# 12V_DC.net
KiCad netlist of a schematic drawn in Altium Designer
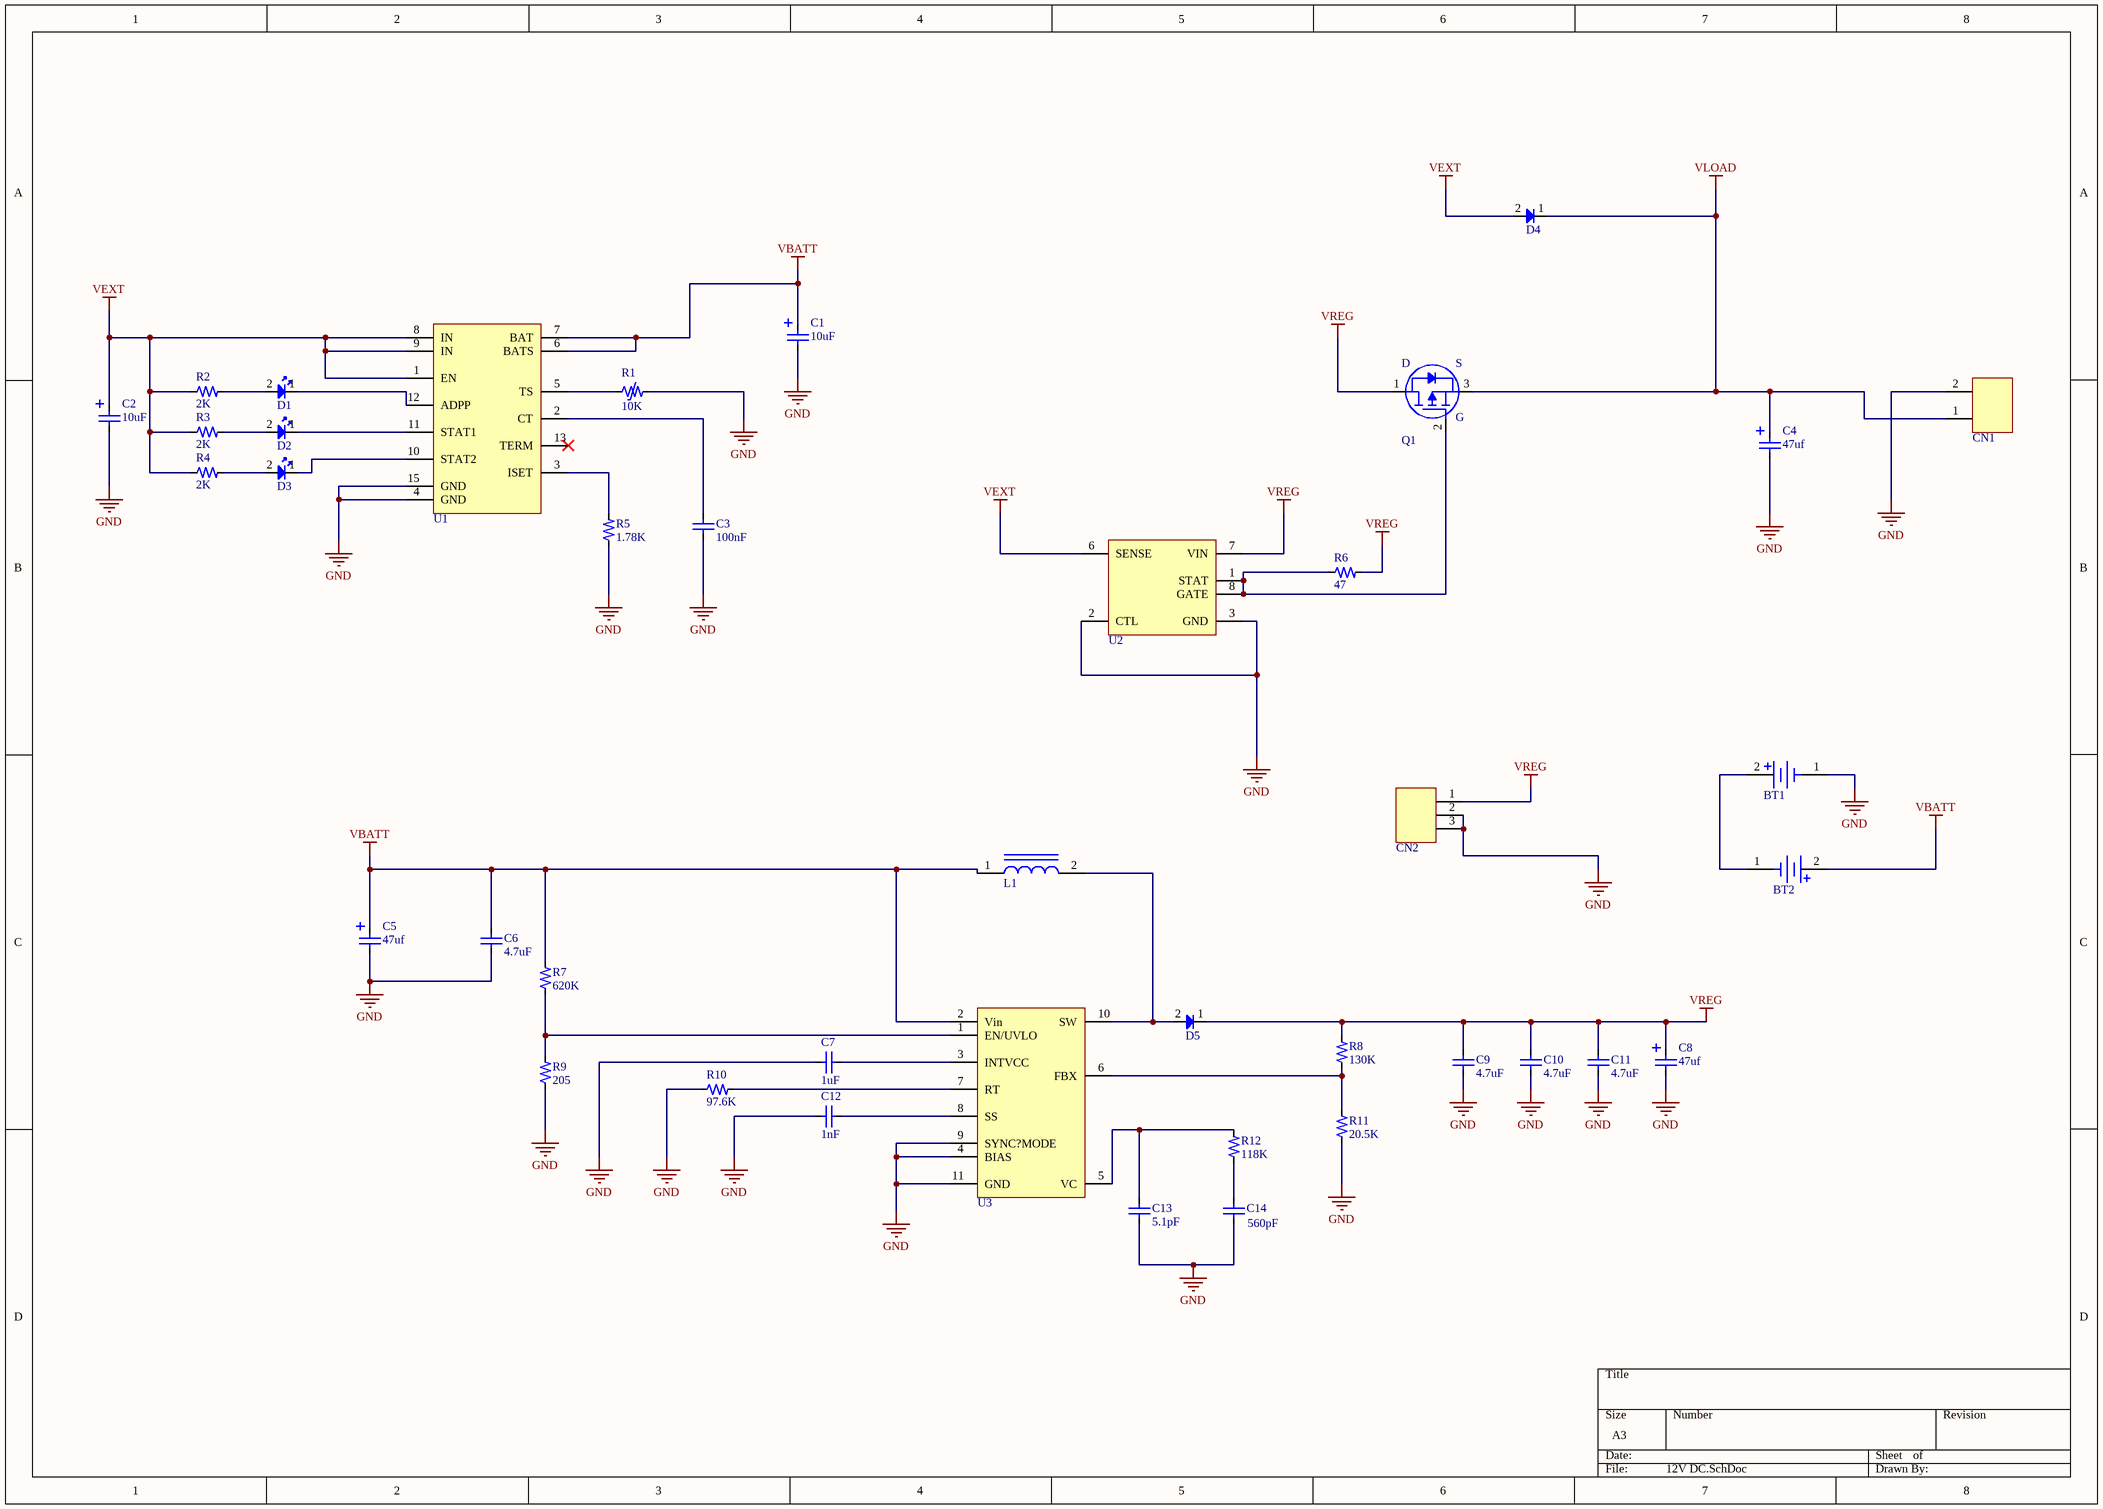
[diagram p0: 12V DC.SchDoc]

(export (version "E")
  (design (tool "Eeschema 10.0.6"))
  (components
    (comp (ref "BT1")
      (value "BK-18650-PC2")
      (footprint "18650")
      (libsource (lib "Database_Libs1") (part "BK-18650-PC2"))
    )
    (comp (ref "BT2")
      (value "BK-18650-PC2")
      (footprint "18650")
      (libsource (lib "Database_Libs1") (part "BK-18650-PC2"))
    )
    (comp (ref "C1")
      (value "10uF")
      (footprint "CAP_3216")
      (fields
        (field (name "VOLTAGE") "10V")
        (field (name "TOLERANCE") "±10%")
        (field (name "Comment") "CAP_POL")
      )
      (libsource (lib "Database_Libs1") (part "CAP_POL"))
    )
    (comp (ref "C2")
      (value "10uF")
      (footprint "CAP_3216")
      (fields
        (field (name "VOLTAGE") "10V")
        (field (name "TOLERANCE") "±10%")
        (field (name "Comment") "CAP_POL")
      )
      (libsource (lib "Database_Libs1") (part "CAP_POL"))
    )
    (comp (ref "C3")
      (value "100nF")
      (footprint "Capacitor_0402")
      (fields
        (field (name "VOLTAGE") "50V")
        (field (name "TOLERANCE") "±10%")
        (field (name "Comment") "Capacitor_0402")
      )
      (libsource (lib "Database_Libs1") (part "Capacitor_0402"))
    )
    (comp (ref "C4")
      (value "47uf")
      (footprint "CAP_1206")
      (fields
        (field (name "VOLTAGE") "6.3V")
        (field (name "TOLERANCE") "±20%")
        (field (name "Comment") "CAP_1206")
      )
      (libsource (lib "Database_Libs1") (part "CAP_1206"))
    )
    (comp (ref "C5")
      (value "47uf")
      (footprint "CAP_1206")
      (fields
        (field (name "VOLTAGE") "6.3V")
        (field (name "TOLERANCE") "±20%")
        (field (name "Comment") "CAP_1206")
      )
      (libsource (lib "Database_Libs1") (part "CAP_1206"))
    )
    (comp (ref "C6")
      (value "4.7uF")
      (footprint "Capacitor_0603")
      (fields
        (field (name "VOLTAGE") "10V")
        (field (name "TOLERANCE") "±10%")
        (field (name "Comment") "Capacitor_0603")
      )
      (libsource (lib "Database_Libs1") (part "Capacitor_0603"))
    )
    (comp (ref "C7")
      (value "1uF")
      (footprint "Capacitor_0402")
      (fields
        (field (name "VOLTAGE") "6.3V")
        (field (name "TOLERANCE") "±10%")
        (field (name "Comment") "Capacitor_0402")
      )
      (libsource (lib "Database_Libs1") (part "Capacitor_0402"))
    )
    (comp (ref "C8")
      (value "47uf")
      (footprint "CAP_1206")
      (fields
        (field (name "VOLTAGE") "6.3V")
        (field (name "TOLERANCE") "±20%")
        (field (name "Comment") "CAP_1206")
      )
      (libsource (lib "Database_Libs1") (part "CAP_1206"))
    )
    (comp (ref "C9")
      (value "4.7uF")
      (footprint "Capacitor_0603")
      (fields
        (field (name "VOLTAGE") "10V")
        (field (name "TOLERANCE") "±10%")
        (field (name "Comment") "Capacitor_0603")
      )
      (libsource (lib "Database_Libs1") (part "Capacitor_0603"))
    )
    (comp (ref "C10")
      (value "4.7uF")
      (footprint "Capacitor_0603")
      (fields
        (field (name "VOLTAGE") "10V")
        (field (name "TOLERANCE") "±10%")
        (field (name "Comment") "Capacitor_0603")
      )
      (libsource (lib "Database_Libs1") (part "Capacitor_0603"))
    )
    (comp (ref "C11")
      (value "4.7uF")
      (footprint "Capacitor_0603")
      (fields
        (field (name "VOLTAGE") "10V")
        (field (name "TOLERANCE") "±10%")
        (field (name "Comment") "Capacitor_0603")
      )
      (libsource (lib "Database_Libs1") (part "Capacitor_0603"))
    )
    (comp (ref "C12")
      (value "1nF")
      (footprint "Capacitor_0402")
      (fields
        (field (name "VOLTAGE") "50v")
        (field (name "TOLERANCE") "±10%")
        (field (name "Comment") "Capacitor_0402")
      )
      (libsource (lib "Database_Libs1") (part "Capacitor_0402"))
    )
    (comp (ref "C13")
      (value "5.1pF")
      (footprint "Capacitor_0402")
      (fields
        (field (name "VOLTAGE") "50V")
        (field (name "TOLERANCE") "±0.25pF")
        (field (name "Comment") "Capacitor_0402")
      )
      (libsource (lib "Database_Libs1") (part "Capacitor_0402"))
    )
    (comp (ref "C14")
      (value "560pF")
      (footprint "Capacitor_0402")
      (fields (field (name "VOLTAGE") "50V") (field (name "Comment") "Capacitor_0402"))
      (libsource (lib "Database_Libs1") (part "Capacitor_0402"))
    )
    (comp (ref "CN1")
      (value "2 Position Wire Terminal")
      (footprint "282834-2")
      (libsource (lib "Database_Libs1") (part "2 Position Wire Terminal"))
    )
    (comp (ref "CN2")
      (value "PJ-202A")
      (footprint "PJ-202A")
      (libsource (lib "Database_Libs1") (part "PJ-202A"))
    )
    (comp (ref "D1")
      (value "LED")
      (footprint "LED_0402")
      (fields (field (name "VOLTAGE") "2V") (field (name "POWER") "0.06W"))
      (libsource (lib "Database_Libs1") (part "LED"))
    )
    (comp (ref "D2")
      (value "LED")
      (footprint "LED_0402")
      (fields (field (name "VOLTAGE") "2V") (field (name "POWER") "0.06W"))
      (libsource (lib "Database_Libs1") (part "LED"))
    )
    (comp (ref "D3")
      (value "LED")
      (footprint "LED_0402")
      (fields (field (name "VOLTAGE") "2V") (field (name "POWER") "0.06W"))
      (libsource (lib "Database_Libs1") (part "LED"))
    )
    (comp (ref "D4")
      (value "CDBA240LL-HF")
      (footprint "DO-214AC")
      (fields (field (name "VOLTAGE") "40v"))
      (libsource (lib "Database_Libs1") (part "CDBA240LL-HF"))
    )
    (comp (ref "D5")
      (value "CDBA240LL-HF")
      (footprint "DO-214AC")
      (fields (field (name "VOLTAGE") "40v"))
      (libsource (lib "Database_Libs1") (part "CDBA240LL-HF"))
    )
    (comp (ref "L1")
      (value "IHLP4040DZER5R6M01")
      (footprint "Inductor_4040")
      (fields (field (name "TOLERANCE") "±20%"))
      (libsource (lib "Database_Libs1") (part "IHLP4040DZER5R6M01"))
    )
    (comp (ref "Q1")
      (value "DMP2045U-7")
      (footprint "SOT-23")
      (description "P-Channel 20 V 4.3A (Ta) 800mW (Ta) Surface Mount SOT-23-3")
      (fields (field (name "VOLTAGE") "20 V"))
      (libsource (lib "Database_Libs1") (part "DMP2045U-7"))
    )
    (comp (ref "R1")
      (value "10K")
      (footprint "Resistor_0402")
      (fields
        (field (name "POWER") "66 mW")
        (field (name "TOLERANCE") "±3%")
        (field (name "Comment") "Thermistor_0402")
      )
      (libsource (lib "Database_Libs1") (part "Thermistor_0402"))
    )
    (comp (ref "R2")
      (value "2K")
      (footprint "Resistor_0603")
      (fields
        (field (name "POWER") "100mW")
        (field (name "TOLERANCE") "±1%")
        (field (name "Comment") "Resistor_0603")
      )
      (libsource (lib "Database_Libs1") (part "Resistor_0603"))
    )
    (comp (ref "R3")
      (value "2K")
      (footprint "Resistor_0603")
      (fields
        (field (name "POWER") "100mW")
        (field (name "TOLERANCE") "±1%")
        (field (name "Comment") "Resistor_0603")
      )
      (libsource (lib "Database_Libs1") (part "Resistor_0603"))
    )
    (comp (ref "R4")
      (value "2K")
      (footprint "Resistor_0603")
      (fields
        (field (name "POWER") "100mW")
        (field (name "TOLERANCE") "±1%")
        (field (name "Comment") "Resistor_0603")
      )
      (libsource (lib "Database_Libs1") (part "Resistor_0603"))
    )
    (comp (ref "R5")
      (value "1.78K")
      (footprint "Resistor_0603")
      (fields
        (field (name "POWER") "100mW")
        (field (name "TOLERANCE") "±1%")
        (field (name "Comment") "Resistor_0603")
      )
      (libsource (lib "Database_Libs1") (part "Resistor_0603"))
    )
    (comp (ref "R6")
      (value "47")
      (footprint "Resistor_0603")
      (fields
        (field (name "POWER") "100mW")
        (field (name "TOLERANCE") "±1%")
        (field (name "Comment") "Resistor_0603")
      )
      (libsource (lib "Database_Libs1") (part "Resistor_0603"))
    )
    (comp (ref "R7")
      (value "620K")
      (footprint "Resistor_0603")
      (fields
        (field (name "POWER") "100mW")
        (field (name "TOLERANCE") "±1%")
        (field (name "Comment") "Resistor_0603")
      )
      (libsource (lib "Database_Libs1") (part "Resistor_0603"))
    )
    (comp (ref "R8")
      (value "130K")
      (footprint "Resistor_0402")
      (fields
        (field (name "POWER") "100mW")
        (field (name "TOLERANCE") "±1%")
        (field (name "Comment") "Resistor_0402")
      )
      (libsource (lib "Database_Libs1") (part "Resistor_0402"))
    )
    (comp (ref "R9")
      (value "205")
      (footprint "Resistor_0603")
      (fields
        (field (name "POWER") "100mW")
        (field (name "TOLERANCE") "±1%")
        (field (name "Comment") "Resistor_0603")
      )
      (libsource (lib "Database_Libs1") (part "Resistor_0603"))
    )
    (comp (ref "R10")
      (value "97.6K")
      (footprint "Resistor_0402")
      (fields
        (field (name "POWER") "63mW")
        (field (name "TOLERANCE") "±1%")
        (field (name "Comment") "Resistor_0402")
      )
      (libsource (lib "Database_Libs1") (part "Resistor_0402"))
    )
    (comp (ref "R11")
      (value "20.5K")
      (footprint "Resistor_0603")
      (fields
        (field (name "POWER") "100mW")
        (field (name "TOLERANCE") "±1%")
        (field (name "Comment") "Resistor_0603")
      )
      (libsource (lib "Database_Libs1") (part "Resistor_0603"))
    )
    (comp (ref "R12")
      (value "118K")
      (footprint "Resistor_0402")
      (fields
        (field (name "POWER") "100mW")
        (field (name "TOLERANCE") "±1%")
        (field (name "Comment") "Resistor_0402")
      )
      (libsource (lib "Database_Libs1") (part "Resistor_0402"))
    )
    (comp (ref "U1")
      (value "AAT3663IWO-8.4-2-T1")
      (footprint "14-TDFN")
      (libsource (lib "Database_Libs1") (part "AAT3663IWO-8.4-2-T1"))
    )
    (comp (ref "U2")
      (value "LTC4414EMS8#PBF")
      (footprint "8-MSOP")
      (libsource (lib "Database_Libs1") (part "LTC4414EMS8#PBF"))
    )
    (comp (ref "U3")
      (value "LT8362EDD#PBF")
      (footprint "10-DFN")
      (libsource (lib "Database_Libs1") (part "LT8362EDD#PBF"))
    )
  )
  (nets
    (net (code "1") (name "GND") (class "Default")
      (node (ref "BT1") (pin "1") (pinfunction "NEG_1") (pintype "passive"))
      (node (ref "C1") (pin "1") (pinfunction "1_1") (pintype "passive"))
      (node (ref "C10") (pin "2") (pinfunction "2_2") (pintype "passive"))
      (node (ref "C11") (pin "1") (pinfunction "1_1") (pintype "passive"))
      (node (ref "C12") (pin "1") (pinfunction "1_1") (pintype "passive"))
      (node (ref "C13") (pin "1") (pinfunction "1_1") (pintype "passive"))
      (node (ref "C14") (pin "1") (pinfunction "1_1") (pintype "passive"))
      (node (ref "C2") (pin "1") (pinfunction "1_1") (pintype "passive"))
      (node (ref "C3") (pin "1") (pinfunction "1_1") (pintype "passive"))
      (node (ref "C4") (pin "1") (pinfunction "1_1") (pintype "passive"))
      (node (ref "C5") (pin "1") (pinfunction "1_1") (pintype "passive"))
      (node (ref "C6") (pin "1") (pinfunction "1_1") (pintype "passive"))
      (node (ref "C7") (pin "1") (pinfunction "1_1") (pintype "passive"))
      (node (ref "C8") (pin "1") (pinfunction "1_1") (pintype "passive"))
      (node (ref "C9") (pin "1") (pinfunction "1_1") (pintype "passive"))
      (node (ref "CN1") (pin "2") (pinfunction "2_2") (pintype "passive"))
      (node (ref "CN2") (pin "2") (pintype "passive"))
      (node (ref "CN2") (pin "3") (pintype "passive"))
      (node (ref "R1") (pin "2") (pinfunction "2_2") (pintype "passive"))
      (node (ref "R10") (pin "1") (pinfunction "1_1") (pintype "passive"))
      (node (ref "R11") (pin "1") (pinfunction "1_1") (pintype "passive"))
      (node (ref "R5") (pin "1") (pinfunction "1_1") (pintype "passive"))
      (node (ref "R9") (pin "1") (pinfunction "1_1") (pintype "passive"))
      (node (ref "U1") (pin "15") (pinfunction "GND_15") (pintype "passive"))
      (node (ref "U1") (pin "4") (pinfunction "GND_4") (pintype "passive"))
      (node (ref "U2") (pin "2") (pinfunction "CTL_2") (pintype "power_in"))
      (node (ref "U2") (pin "3") (pinfunction "GND_3") (pintype "power_in"))
      (node (ref "U3") (pin "11") (pinfunction "GND_11") (pintype "passive"))
      (node (ref "U3") (pin "4") (pinfunction "BIAS_4") (pintype "passive"))
      (node (ref "U3") (pin "9") (pinfunction "SYNC?MODE_9") (pintype "passive"))
    )
    (net (code "2") (name "Net-(BT1-POS)") (class "Default")
      (node (ref "BT1") (pin "2") (pinfunction "POS_2") (pintype "passive"))
      (node (ref "BT2") (pin "1") (pinfunction "NEG_1") (pintype "passive"))
    )
    (net (code "3") (name "Net-(C14-Pad2)") (class "Default")
      (node (ref "C14") (pin "2") (pinfunction "2_2") (pintype "passive"))
      (node (ref "R12") (pin "1") (pinfunction "1_1") (pintype "passive"))
    )
    (net (code "4") (name "Net-(D1-Pad2)") (class "Default")
      (node (ref "D1") (pin "2") (pinfunction "2_2") (pintype "passive"))
      (node (ref "R2") (pin "2") (pinfunction "2_2") (pintype "passive"))
    )
    (net (code "5") (name "Net-(D2-Pad2)") (class "Default")
      (node (ref "D2") (pin "2") (pinfunction "2_2") (pintype "passive"))
      (node (ref "R3") (pin "2") (pinfunction "2_2") (pintype "passive"))
    )
    (net (code "6") (name "Net-(D3-Pad2)") (class "Default")
      (node (ref "D3") (pin "2") (pinfunction "2_2") (pintype "passive"))
      (node (ref "R4") (pin "2") (pinfunction "2_2") (pintype "passive"))
    )
    (net (code "7") (name "Net-(Q1-G)") (class "Default")
      (node (ref "Q1") (pin "2") (pinfunction "G_2") (pintype "passive"))
      (node (ref "R6") (pin "1") (pinfunction "1_1") (pintype "passive"))
      (node (ref "U2") (pin "1") (pinfunction "STAT_1") (pintype "power_in"))
      (node (ref "U2") (pin "8") (pinfunction "GATE_8") (pintype "passive"))
    )
    (net (code "8") (name "Net-(U1-ADPP)") (class "Default")
      (node (ref "D1") (pin "1") (pinfunction "1_1") (pintype "passive"))
      (node (ref "U1") (pin "12") (pinfunction "ADPP_12") (pintype "passive"))
    )
    (net (code "9") (name "Net-(U1-CT)") (class "Default")
      (node (ref "C3") (pin "2") (pinfunction "2_2") (pintype "passive"))
      (node (ref "U1") (pin "2") (pinfunction "CT_2") (pintype "passive"))
    )
    (net (code "10") (name "Net-(U1-ISET)") (class "Default")
      (node (ref "R5") (pin "2") (pinfunction "2_2") (pintype "passive"))
      (node (ref "U1") (pin "3") (pinfunction "ISET_3") (pintype "passive"))
    )
    (net (code "11") (name "Net-(U1-STAT1)") (class "Default")
      (node (ref "D2") (pin "1") (pinfunction "1_1") (pintype "passive"))
      (node (ref "U1") (pin "11") (pinfunction "STAT1_11") (pintype "passive"))
    )
    (net (code "12") (name "Net-(U1-STAT2)") (class "Default")
      (node (ref "D3") (pin "1") (pinfunction "1_1") (pintype "passive"))
      (node (ref "U1") (pin "10") (pinfunction "STAT2_10") (pintype "passive"))
    )
    (net (code "13") (name "Net-(U1-TS)") (class "Default")
      (node (ref "R1") (pin "1") (pinfunction "1_1") (pintype "passive"))
      (node (ref "U1") (pin "5") (pinfunction "TS_5") (pintype "passive"))
    )
    (net (code "14") (name "Net-(U3-EN{slash}UVLO)") (class "Default")
      (node (ref "R7") (pin "1") (pinfunction "1_1") (pintype "passive"))
      (node (ref "R9") (pin "2") (pinfunction "2_2") (pintype "passive"))
      (node (ref "U3") (pin "1") (pinfunction "EN/UVLO_1") (pintype "passive"))
    )
    (net (code "15") (name "Net-(U3-FBX)") (class "Default")
      (node (ref "R11") (pin "2") (pinfunction "2_2") (pintype "passive"))
      (node (ref "R8") (pin "1") (pinfunction "1_1") (pintype "passive"))
      (node (ref "U3") (pin "6") (pinfunction "FBX_6") (pintype "passive"))
    )
    (net (code "16") (name "Net-(U3-INTVCC)") (class "Default")
      (node (ref "C7") (pin "2") (pinfunction "2_2") (pintype "passive"))
      (node (ref "U3") (pin "3") (pinfunction "INTVCC_3") (pintype "passive"))
    )
    (net (code "17") (name "Net-(U3-RT)") (class "Default")
      (node (ref "R10") (pin "2") (pinfunction "2_2") (pintype "passive"))
      (node (ref "U3") (pin "7") (pinfunction "RT_7") (pintype "passive"))
    )
    (net (code "18") (name "Net-(U3-SS)") (class "Default")
      (node (ref "C12") (pin "2") (pinfunction "2_2") (pintype "passive"))
      (node (ref "U3") (pin "8") (pinfunction "SS_8") (pintype "passive"))
    )
    (net (code "19") (name "Net-(U3-SW)") (class "Default")
      (node (ref "D5") (pin "2") (pinfunction "2_2") (pintype "passive"))
      (node (ref "L1") (pin "2") (pinfunction "2_2") (pintype "passive"))
      (node (ref "U3") (pin "10") (pinfunction "SW_10") (pintype "passive"))
    )
    (net (code "20") (name "Net-(U3-VC)") (class "Default")
      (node (ref "C13") (pin "2") (pinfunction "2_2") (pintype "passive"))
      (node (ref "R12") (pin "2") (pinfunction "2_2") (pintype "passive"))
      (node (ref "U3") (pin "5") (pinfunction "VC_5") (pintype "passive"))
    )
    (net (code "21") (name "VBATT") (class "Default")
      (node (ref "BT2") (pin "2") (pinfunction "POS_2") (pintype "passive"))
      (node (ref "C1") (pin "2") (pinfunction "2_2") (pintype "passive"))
      (node (ref "C5") (pin "2") (pinfunction "2_2") (pintype "passive"))
      (node (ref "C6") (pin "2") (pinfunction "2_2") (pintype "passive"))
      (node (ref "L1") (pin "1") (pinfunction "1_1") (pintype "passive"))
      (node (ref "R7") (pin "2") (pinfunction "2_2") (pintype "passive"))
      (node (ref "U1") (pin "6") (pinfunction "BATS_6") (pintype "passive"))
      (node (ref "U1") (pin "7") (pinfunction "BAT_7") (pintype "passive"))
      (node (ref "U3") (pin "2") (pinfunction "Vin_2") (pintype "passive"))
    )
    (net (code "22") (name "VEXT") (class "Default")
      (node (ref "C2") (pin "2") (pinfunction "2_2") (pintype "passive"))
      (node (ref "D4") (pin "2") (pinfunction "2_2") (pintype "passive"))
      (node (ref "R2") (pin "1") (pinfunction "1_1") (pintype "passive"))
      (node (ref "R3") (pin "1") (pinfunction "1_1") (pintype "passive"))
      (node (ref "R4") (pin "1") (pinfunction "1_1") (pintype "passive"))
      (node (ref "U1") (pin "1") (pinfunction "EN_1") (pintype "passive"))
      (node (ref "U1") (pin "8") (pinfunction "IN_8") (pintype "passive"))
      (node (ref "U1") (pin "9") (pinfunction "IN_9") (pintype "passive"))
      (node (ref "U2") (pin "6") (pinfunction "SENSE_6") (pintype "power_in"))
    )
    (net (code "23") (name "VLOAD") (class "Default")
      (node (ref "C4") (pin "2") (pinfunction "2_2") (pintype "passive"))
      (node (ref "CN1") (pin "1") (pinfunction "1_1") (pintype "passive"))
      (node (ref "D4") (pin "1") (pinfunction "1_1") (pintype "passive"))
      (node (ref "Q1") (pin "3") (pinfunction "S_3") (pintype "passive"))
    )
    (net (code "24") (name "VREG") (class "Default")
      (node (ref "C10") (pin "1") (pinfunction "1_1") (pintype "passive"))
      (node (ref "C11") (pin "2") (pinfunction "2_2") (pintype "passive"))
      (node (ref "C8") (pin "2") (pinfunction "2_2") (pintype "passive"))
      (node (ref "C9") (pin "2") (pinfunction "2_2") (pintype "passive"))
      (node (ref "CN2") (pin "1") (pintype "passive"))
      (node (ref "D5") (pin "1") (pinfunction "1_1") (pintype "passive"))
      (node (ref "Q1") (pin "1") (pinfunction "D_1") (pintype "passive"))
      (node (ref "R6") (pin "2") (pinfunction "2_2") (pintype "passive"))
      (node (ref "R8") (pin "2") (pinfunction "2_2") (pintype "passive"))
      (node (ref "U2") (pin "7") (pinfunction "VIN_7") (pintype "power_in"))
    )
    (net (code "25") (name "unconnected-(U1-TERM-Pad13)") (class "Default")
      (node (ref "U1") (pin "13") (pinfunction "TERM_13") (pintype "passive+no_connect"))
    )
  )
)
